# MDM_V3_Connectorx6_A.net
KiCad netlist of a schematic drawn in EAGLE
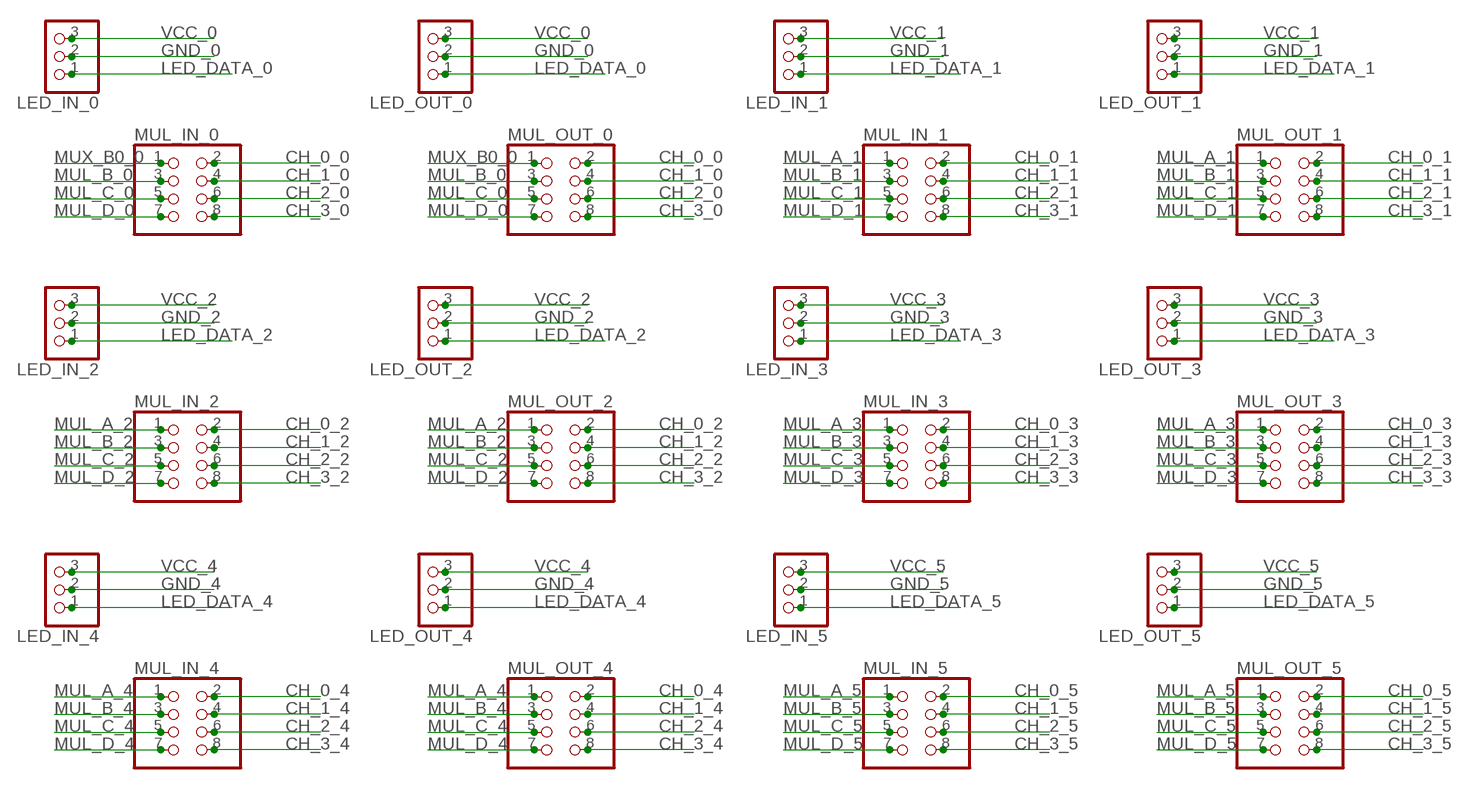
[diagram p0: schematic, sheet 1]

(export (version "E")
  (design (tool "Eeschema 10.0.6"))
  (components
    (comp (ref "LED_IN_0")
      (value "PINHD-1X3")
      (footprint "eagle-import:1X03")
      (libsource (lib "eagle-import") (part "PINHD-1X3"))
    )
    (comp (ref "LED_IN_1")
      (value "PINHD-1X3")
      (footprint "eagle-import:1X03")
      (libsource (lib "eagle-import") (part "PINHD-1X3"))
    )
    (comp (ref "LED_IN_2")
      (value "PINHD-1X3")
      (footprint "eagle-import:1X03")
      (libsource (lib "eagle-import") (part "PINHD-1X3"))
    )
    (comp (ref "LED_IN_3")
      (value "PINHD-1X3")
      (footprint "eagle-import:1X03")
      (libsource (lib "eagle-import") (part "PINHD-1X3"))
    )
    (comp (ref "LED_IN_4")
      (value "PINHD-1X3")
      (footprint "eagle-import:1X03")
      (libsource (lib "eagle-import") (part "PINHD-1X3"))
    )
    (comp (ref "LED_IN_5")
      (value "PINHD-1X3")
      (footprint "eagle-import:1X03")
      (libsource (lib "eagle-import") (part "PINHD-1X3"))
    )
    (comp (ref "LED_OUT_0")
      (value "PINHD-1X3")
      (footprint "eagle-import:1X03")
      (libsource (lib "eagle-import") (part "PINHD-1X3"))
    )
    (comp (ref "LED_OUT_1")
      (value "PINHD-1X3")
      (footprint "eagle-import:1X03")
      (libsource (lib "eagle-import") (part "PINHD-1X3"))
    )
    (comp (ref "LED_OUT_2")
      (value "PINHD-1X3")
      (footprint "eagle-import:1X03")
      (libsource (lib "eagle-import") (part "PINHD-1X3"))
    )
    (comp (ref "LED_OUT_3")
      (value "PINHD-1X3")
      (footprint "eagle-import:1X03")
      (libsource (lib "eagle-import") (part "PINHD-1X3"))
    )
    (comp (ref "LED_OUT_4")
      (value "PINHD-1X3")
      (footprint "eagle-import:1X03")
      (libsource (lib "eagle-import") (part "PINHD-1X3"))
    )
    (comp (ref "LED_OUT_5")
      (value "PINHD-1X3")
      (footprint "eagle-import:1X03")
      (libsource (lib "eagle-import") (part "PINHD-1X3"))
    )
    (comp (ref "MUL_IN_0")
      (value "PINHD-2X4")
      (footprint "eagle-import:2X04")
      (libsource (lib "eagle-import") (part "PINHD-2X4"))
    )
    (comp (ref "MUL_IN_1")
      (value "PINHD-2X4")
      (footprint "eagle-import:2X04")
      (libsource (lib "eagle-import") (part "PINHD-2X4"))
    )
    (comp (ref "MUL_IN_2")
      (value "PINHD-2X4")
      (footprint "eagle-import:2X04")
      (libsource (lib "eagle-import") (part "PINHD-2X4"))
    )
    (comp (ref "MUL_IN_3")
      (value "PINHD-2X4")
      (footprint "eagle-import:2X04")
      (libsource (lib "eagle-import") (part "PINHD-2X4"))
    )
    (comp (ref "MUL_IN_4")
      (value "PINHD-2X4")
      (footprint "eagle-import:2X04")
      (libsource (lib "eagle-import") (part "PINHD-2X4"))
    )
    (comp (ref "MUL_IN_5")
      (value "PINHD-2X4")
      (footprint "eagle-import:2X04")
      (libsource (lib "eagle-import") (part "PINHD-2X4"))
    )
    (comp (ref "MUL_OUT_0")
      (value "PINHD-2X4")
      (footprint "eagle-import:2X04")
      (libsource (lib "eagle-import") (part "PINHD-2X4"))
    )
    (comp (ref "MUL_OUT_1")
      (value "PINHD-2X4")
      (footprint "eagle-import:2X04")
      (libsource (lib "eagle-import") (part "PINHD-2X4"))
    )
    (comp (ref "MUL_OUT_2")
      (value "PINHD-2X4")
      (footprint "eagle-import:2X04")
      (libsource (lib "eagle-import") (part "PINHD-2X4"))
    )
    (comp (ref "MUL_OUT_3")
      (value "PINHD-2X4")
      (footprint "eagle-import:2X04")
      (libsource (lib "eagle-import") (part "PINHD-2X4"))
    )
    (comp (ref "MUL_OUT_4")
      (value "PINHD-2X4")
      (footprint "eagle-import:2X04")
      (libsource (lib "eagle-import") (part "PINHD-2X4"))
    )
    (comp (ref "MUL_OUT_5")
      (value "PINHD-2X4")
      (footprint "eagle-import:2X04")
      (libsource (lib "eagle-import") (part "PINHD-2X4"))
    )
  )
  (nets
    (net (code "1") (name "/CH_0_0") (class "Default")
      (node (ref "MUL_IN_0") (pin "2") (pinfunction "2_2") (pintype "passive"))
      (node (ref "MUL_OUT_0") (pin "2") (pinfunction "2_2") (pintype "passive"))
    )
    (net (code "2") (name "/CH_0_1") (class "Default")
      (node (ref "MUL_IN_1") (pin "2") (pinfunction "2_2") (pintype "passive"))
      (node (ref "MUL_OUT_1") (pin "2") (pinfunction "2_2") (pintype "passive"))
    )
    (net (code "3") (name "/CH_0_2") (class "Default")
      (node (ref "MUL_IN_2") (pin "2") (pinfunction "2_2") (pintype "passive"))
      (node (ref "MUL_OUT_2") (pin "2") (pinfunction "2_2") (pintype "passive"))
    )
    (net (code "4") (name "/CH_0_3") (class "Default")
      (node (ref "MUL_IN_3") (pin "2") (pinfunction "2_2") (pintype "passive"))
      (node (ref "MUL_OUT_3") (pin "2") (pinfunction "2_2") (pintype "passive"))
    )
    (net (code "5") (name "/CH_0_4") (class "Default")
      (node (ref "MUL_IN_4") (pin "2") (pinfunction "2_2") (pintype "passive"))
      (node (ref "MUL_OUT_4") (pin "2") (pinfunction "2_2") (pintype "passive"))
    )
    (net (code "6") (name "/CH_0_5") (class "Default")
      (node (ref "MUL_IN_5") (pin "2") (pinfunction "2_2") (pintype "passive"))
      (node (ref "MUL_OUT_5") (pin "2") (pinfunction "2_2") (pintype "passive"))
    )
    (net (code "7") (name "/CH_1_0") (class "Default")
      (node (ref "MUL_IN_0") (pin "4") (pinfunction "4_4") (pintype "passive"))
      (node (ref "MUL_OUT_0") (pin "4") (pinfunction "4_4") (pintype "passive"))
    )
    (net (code "8") (name "/CH_1_1") (class "Default")
      (node (ref "MUL_IN_1") (pin "4") (pinfunction "4_4") (pintype "passive"))
      (node (ref "MUL_OUT_1") (pin "4") (pinfunction "4_4") (pintype "passive"))
    )
    (net (code "9") (name "/CH_1_2") (class "Default")
      (node (ref "MUL_IN_2") (pin "4") (pinfunction "4_4") (pintype "passive"))
      (node (ref "MUL_OUT_2") (pin "4") (pinfunction "4_4") (pintype "passive"))
    )
    (net (code "10") (name "/CH_1_3") (class "Default")
      (node (ref "MUL_IN_3") (pin "4") (pinfunction "4_4") (pintype "passive"))
      (node (ref "MUL_OUT_3") (pin "4") (pinfunction "4_4") (pintype "passive"))
    )
    (net (code "11") (name "/CH_1_4") (class "Default")
      (node (ref "MUL_IN_4") (pin "4") (pinfunction "4_4") (pintype "passive"))
      (node (ref "MUL_OUT_4") (pin "4") (pinfunction "4_4") (pintype "passive"))
    )
    (net (code "12") (name "/CH_1_5") (class "Default")
      (node (ref "MUL_IN_5") (pin "4") (pinfunction "4_4") (pintype "passive"))
      (node (ref "MUL_OUT_5") (pin "4") (pinfunction "4_4") (pintype "passive"))
    )
    (net (code "13") (name "/CH_2_0") (class "Default")
      (node (ref "MUL_IN_0") (pin "6") (pinfunction "6_6") (pintype "passive"))
      (node (ref "MUL_OUT_0") (pin "6") (pinfunction "6_6") (pintype "passive"))
    )
    (net (code "14") (name "/CH_2_1") (class "Default")
      (node (ref "MUL_IN_1") (pin "6") (pinfunction "6_6") (pintype "passive"))
      (node (ref "MUL_OUT_1") (pin "6") (pinfunction "6_6") (pintype "passive"))
    )
    (net (code "15") (name "/CH_2_2") (class "Default")
      (node (ref "MUL_IN_2") (pin "6") (pinfunction "6_6") (pintype "passive"))
      (node (ref "MUL_OUT_2") (pin "6") (pinfunction "6_6") (pintype "passive"))
    )
    (net (code "16") (name "/CH_2_3") (class "Default")
      (node (ref "MUL_IN_3") (pin "6") (pinfunction "6_6") (pintype "passive"))
      (node (ref "MUL_OUT_3") (pin "6") (pinfunction "6_6") (pintype "passive"))
    )
    (net (code "17") (name "/CH_2_4") (class "Default")
      (node (ref "MUL_IN_4") (pin "6") (pinfunction "6_6") (pintype "passive"))
      (node (ref "MUL_OUT_4") (pin "6") (pinfunction "6_6") (pintype "passive"))
    )
    (net (code "18") (name "/CH_2_5") (class "Default")
      (node (ref "MUL_IN_5") (pin "6") (pinfunction "6_6") (pintype "passive"))
      (node (ref "MUL_OUT_5") (pin "6") (pinfunction "6_6") (pintype "passive"))
    )
    (net (code "19") (name "/CH_3_0") (class "Default")
      (node (ref "MUL_IN_0") (pin "8") (pinfunction "8_8") (pintype "passive"))
      (node (ref "MUL_OUT_0") (pin "8") (pinfunction "8_8") (pintype "passive"))
    )
    (net (code "20") (name "/CH_3_1") (class "Default")
      (node (ref "MUL_IN_1") (pin "8") (pinfunction "8_8") (pintype "passive"))
      (node (ref "MUL_OUT_1") (pin "8") (pinfunction "8_8") (pintype "passive"))
    )
    (net (code "21") (name "/CH_3_2") (class "Default")
      (node (ref "MUL_IN_2") (pin "8") (pinfunction "8_8") (pintype "passive"))
      (node (ref "MUL_OUT_2") (pin "8") (pinfunction "8_8") (pintype "passive"))
    )
    (net (code "22") (name "/CH_3_3") (class "Default")
      (node (ref "MUL_IN_3") (pin "8") (pinfunction "8_8") (pintype "passive"))
      (node (ref "MUL_OUT_3") (pin "8") (pinfunction "8_8") (pintype "passive"))
    )
    (net (code "23") (name "/CH_3_4") (class "Default")
      (node (ref "MUL_IN_4") (pin "8") (pinfunction "8_8") (pintype "passive"))
      (node (ref "MUL_OUT_4") (pin "8") (pinfunction "8_8") (pintype "passive"))
    )
    (net (code "24") (name "/CH_3_5") (class "Default")
      (node (ref "MUL_IN_5") (pin "8") (pinfunction "8_8") (pintype "passive"))
      (node (ref "MUL_OUT_5") (pin "8") (pinfunction "8_8") (pintype "passive"))
    )
    (net (code "25") (name "/GND_0") (class "Default")
      (node (ref "LED_IN_0") (pin "2") (pinfunction "2_2") (pintype "passive"))
      (node (ref "LED_OUT_0") (pin "2") (pinfunction "2_2") (pintype "passive"))
    )
    (net (code "26") (name "/GND_1") (class "Default")
      (node (ref "LED_IN_1") (pin "2") (pinfunction "2_2") (pintype "passive"))
      (node (ref "LED_OUT_1") (pin "2") (pinfunction "2_2") (pintype "passive"))
    )
    (net (code "27") (name "/GND_2") (class "Default")
      (node (ref "LED_IN_2") (pin "2") (pinfunction "2_2") (pintype "passive"))
      (node (ref "LED_OUT_2") (pin "2") (pinfunction "2_2") (pintype "passive"))
    )
    (net (code "28") (name "/GND_3") (class "Default")
      (node (ref "LED_IN_3") (pin "2") (pinfunction "2_2") (pintype "passive"))
      (node (ref "LED_OUT_3") (pin "2") (pinfunction "2_2") (pintype "passive"))
    )
    (net (code "29") (name "/GND_4") (class "Default")
      (node (ref "LED_IN_4") (pin "2") (pinfunction "2_2") (pintype "passive"))
      (node (ref "LED_OUT_4") (pin "2") (pinfunction "2_2") (pintype "passive"))
    )
    (net (code "30") (name "/GND_5") (class "Default")
      (node (ref "LED_IN_5") (pin "2") (pinfunction "2_2") (pintype "passive"))
      (node (ref "LED_OUT_5") (pin "2") (pinfunction "2_2") (pintype "passive"))
    )
    (net (code "31") (name "/LED_DATA_0") (class "Default")
      (node (ref "LED_IN_0") (pin "1") (pinfunction "1_1") (pintype "passive"))
      (node (ref "LED_OUT_0") (pin "1") (pinfunction "1_1") (pintype "passive"))
    )
    (net (code "32") (name "/LED_DATA_1") (class "Default")
      (node (ref "LED_IN_1") (pin "1") (pinfunction "1_1") (pintype "passive"))
      (node (ref "LED_OUT_1") (pin "1") (pinfunction "1_1") (pintype "passive"))
    )
    (net (code "33") (name "/LED_DATA_2") (class "Default")
      (node (ref "LED_IN_2") (pin "1") (pinfunction "1_1") (pintype "passive"))
      (node (ref "LED_OUT_2") (pin "1") (pinfunction "1_1") (pintype "passive"))
    )
    (net (code "34") (name "/LED_DATA_3") (class "Default")
      (node (ref "LED_IN_3") (pin "1") (pinfunction "1_1") (pintype "passive"))
      (node (ref "LED_OUT_3") (pin "1") (pinfunction "1_1") (pintype "passive"))
    )
    (net (code "35") (name "/LED_DATA_4") (class "Default")
      (node (ref "LED_IN_4") (pin "1") (pinfunction "1_1") (pintype "passive"))
      (node (ref "LED_OUT_4") (pin "1") (pinfunction "1_1") (pintype "passive"))
    )
    (net (code "36") (name "/LED_DATA_5") (class "Default")
      (node (ref "LED_IN_5") (pin "1") (pinfunction "1_1") (pintype "passive"))
      (node (ref "LED_OUT_5") (pin "1") (pinfunction "1_1") (pintype "passive"))
    )
    (net (code "37") (name "/MUL_A_1") (class "Default")
      (node (ref "MUL_IN_1") (pin "1") (pinfunction "1_1") (pintype "passive"))
      (node (ref "MUL_OUT_1") (pin "1") (pinfunction "1_1") (pintype "passive"))
    )
    (net (code "38") (name "/MUL_A_2") (class "Default")
      (node (ref "MUL_IN_2") (pin "1") (pinfunction "1_1") (pintype "passive"))
      (node (ref "MUL_OUT_2") (pin "1") (pinfunction "1_1") (pintype "passive"))
    )
    (net (code "39") (name "/MUL_A_3") (class "Default")
      (node (ref "MUL_IN_3") (pin "1") (pinfunction "1_1") (pintype "passive"))
      (node (ref "MUL_OUT_3") (pin "1") (pinfunction "1_1") (pintype "passive"))
    )
    (net (code "40") (name "/MUL_A_4") (class "Default")
      (node (ref "MUL_IN_4") (pin "1") (pinfunction "1_1") (pintype "passive"))
      (node (ref "MUL_OUT_4") (pin "1") (pinfunction "1_1") (pintype "passive"))
    )
    (net (code "41") (name "/MUL_A_5") (class "Default")
      (node (ref "MUL_IN_5") (pin "1") (pinfunction "1_1") (pintype "passive"))
      (node (ref "MUL_OUT_5") (pin "1") (pinfunction "1_1") (pintype "passive"))
    )
    (net (code "42") (name "/MUL_B_0") (class "Default")
      (node (ref "MUL_IN_0") (pin "3") (pinfunction "3_3") (pintype "passive"))
      (node (ref "MUL_OUT_0") (pin "3") (pinfunction "3_3") (pintype "passive"))
    )
    (net (code "43") (name "/MUL_B_1") (class "Default")
      (node (ref "MUL_IN_1") (pin "3") (pinfunction "3_3") (pintype "passive"))
      (node (ref "MUL_OUT_1") (pin "3") (pinfunction "3_3") (pintype "passive"))
    )
    (net (code "44") (name "/MUL_B_2") (class "Default")
      (node (ref "MUL_IN_2") (pin "3") (pinfunction "3_3") (pintype "passive"))
      (node (ref "MUL_OUT_2") (pin "3") (pinfunction "3_3") (pintype "passive"))
    )
    (net (code "45") (name "/MUL_B_3") (class "Default")
      (node (ref "MUL_IN_3") (pin "3") (pinfunction "3_3") (pintype "passive"))
      (node (ref "MUL_OUT_3") (pin "3") (pinfunction "3_3") (pintype "passive"))
    )
    (net (code "46") (name "/MUL_B_4") (class "Default")
      (node (ref "MUL_IN_4") (pin "3") (pinfunction "3_3") (pintype "passive"))
      (node (ref "MUL_OUT_4") (pin "3") (pinfunction "3_3") (pintype "passive"))
    )
    (net (code "47") (name "/MUL_B_5") (class "Default")
      (node (ref "MUL_IN_5") (pin "3") (pinfunction "3_3") (pintype "passive"))
      (node (ref "MUL_OUT_5") (pin "3") (pinfunction "3_3") (pintype "passive"))
    )
    (net (code "48") (name "/MUL_C_0") (class "Default")
      (node (ref "MUL_IN_0") (pin "5") (pinfunction "5_5") (pintype "passive"))
      (node (ref "MUL_OUT_0") (pin "5") (pinfunction "5_5") (pintype "passive"))
    )
    (net (code "49") (name "/MUL_C_1") (class "Default")
      (node (ref "MUL_IN_1") (pin "5") (pinfunction "5_5") (pintype "passive"))
      (node (ref "MUL_OUT_1") (pin "5") (pinfunction "5_5") (pintype "passive"))
    )
    (net (code "50") (name "/MUL_C_2") (class "Default")
      (node (ref "MUL_IN_2") (pin "5") (pinfunction "5_5") (pintype "passive"))
      (node (ref "MUL_OUT_2") (pin "5") (pinfunction "5_5") (pintype "passive"))
    )
    (net (code "51") (name "/MUL_C_3") (class "Default")
      (node (ref "MUL_IN_3") (pin "5") (pinfunction "5_5") (pintype "passive"))
      (node (ref "MUL_OUT_3") (pin "5") (pinfunction "5_5") (pintype "passive"))
    )
    (net (code "52") (name "/MUL_C_4") (class "Default")
      (node (ref "MUL_IN_4") (pin "5") (pinfunction "5_5") (pintype "passive"))
      (node (ref "MUL_OUT_4") (pin "5") (pinfunction "5_5") (pintype "passive"))
    )
    (net (code "53") (name "/MUL_C_5") (class "Default")
      (node (ref "MUL_IN_5") (pin "5") (pinfunction "5_5") (pintype "passive"))
      (node (ref "MUL_OUT_5") (pin "5") (pinfunction "5_5") (pintype "passive"))
    )
    (net (code "54") (name "/MUL_D_0") (class "Default")
      (node (ref "MUL_IN_0") (pin "7") (pinfunction "7_7") (pintype "passive"))
      (node (ref "MUL_OUT_0") (pin "7") (pinfunction "7_7") (pintype "passive"))
    )
    (net (code "55") (name "/MUL_D_1") (class "Default")
      (node (ref "MUL_IN_1") (pin "7") (pinfunction "7_7") (pintype "passive"))
      (node (ref "MUL_OUT_1") (pin "7") (pinfunction "7_7") (pintype "passive"))
    )
    (net (code "56") (name "/MUL_D_2") (class "Default")
      (node (ref "MUL_IN_2") (pin "7") (pinfunction "7_7") (pintype "passive"))
      (node (ref "MUL_OUT_2") (pin "7") (pinfunction "7_7") (pintype "passive"))
    )
    (net (code "57") (name "/MUL_D_3") (class "Default")
      (node (ref "MUL_IN_3") (pin "7") (pinfunction "7_7") (pintype "passive"))
      (node (ref "MUL_OUT_3") (pin "7") (pinfunction "7_7") (pintype "passive"))
    )
    (net (code "58") (name "/MUL_D_4") (class "Default")
      (node (ref "MUL_IN_4") (pin "7") (pinfunction "7_7") (pintype "passive"))
      (node (ref "MUL_OUT_4") (pin "7") (pinfunction "7_7") (pintype "passive"))
    )
    (net (code "59") (name "/MUL_D_5") (class "Default")
      (node (ref "MUL_IN_5") (pin "7") (pinfunction "7_7") (pintype "passive"))
      (node (ref "MUL_OUT_5") (pin "7") (pinfunction "7_7") (pintype "passive"))
    )
    (net (code "60") (name "/MUX_B0_0") (class "Default")
      (node (ref "MUL_IN_0") (pin "1") (pinfunction "1_1") (pintype "passive"))
      (node (ref "MUL_OUT_0") (pin "1") (pinfunction "1_1") (pintype "passive"))
    )
    (net (code "61") (name "/VCC_0") (class "Default")
      (node (ref "LED_IN_0") (pin "3") (pinfunction "3_3") (pintype "passive"))
      (node (ref "LED_OUT_0") (pin "3") (pinfunction "3_3") (pintype "passive"))
    )
    (net (code "62") (name "/VCC_1") (class "Default")
      (node (ref "LED_IN_1") (pin "3") (pinfunction "3_3") (pintype "passive"))
      (node (ref "LED_OUT_1") (pin "3") (pinfunction "3_3") (pintype "passive"))
    )
    (net (code "63") (name "/VCC_2") (class "Default")
      (node (ref "LED_IN_2") (pin "3") (pinfunction "3_3") (pintype "passive"))
      (node (ref "LED_OUT_2") (pin "3") (pinfunction "3_3") (pintype "passive"))
    )
    (net (code "64") (name "/VCC_3") (class "Default")
      (node (ref "LED_IN_3") (pin "3") (pinfunction "3_3") (pintype "passive"))
      (node (ref "LED_OUT_3") (pin "3") (pinfunction "3_3") (pintype "passive"))
    )
    (net (code "65") (name "/VCC_4") (class "Default")
      (node (ref "LED_IN_4") (pin "3") (pinfunction "3_3") (pintype "passive"))
      (node (ref "LED_OUT_4") (pin "3") (pinfunction "3_3") (pintype "passive"))
    )
    (net (code "66") (name "/VCC_5") (class "Default")
      (node (ref "LED_IN_5") (pin "3") (pinfunction "3_3") (pintype "passive"))
      (node (ref "LED_OUT_5") (pin "3") (pinfunction "3_3") (pintype "passive"))
    )
  )
)
